# schichor_BP_schema.net
KiCad netlist of a schematic drawn in EAGLE
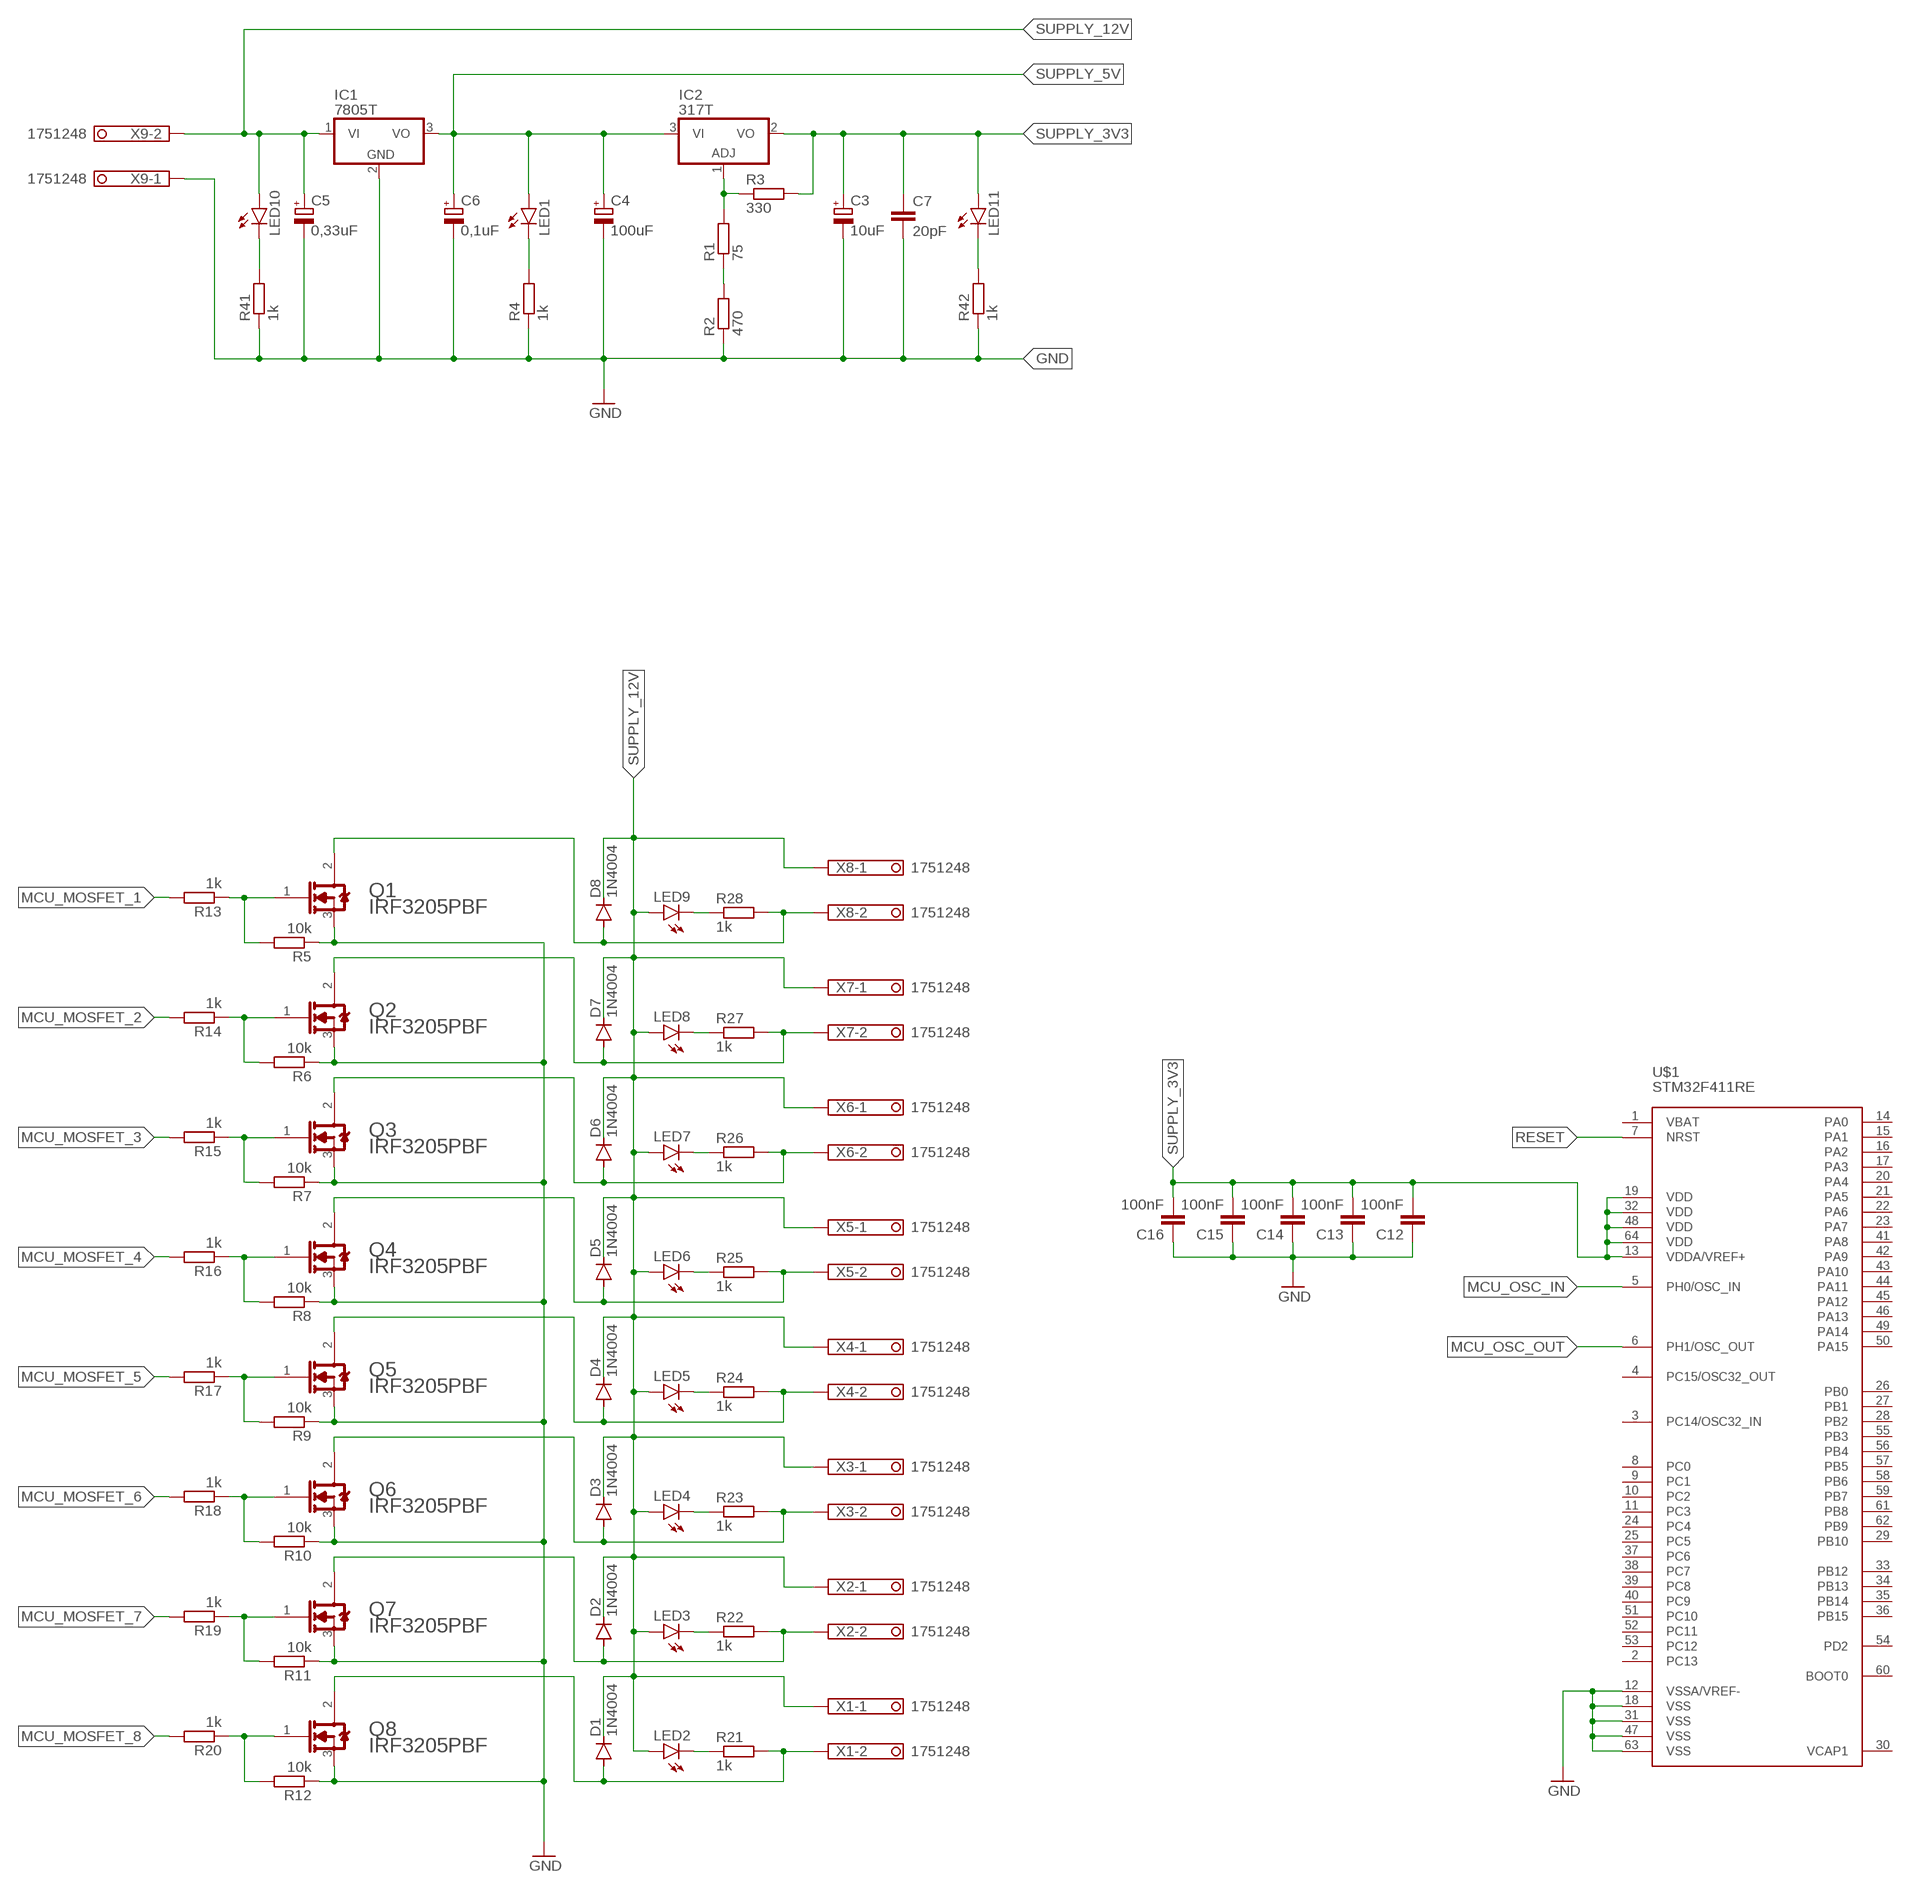
[diagram p0: schematic, sheet 1, part 1 of 2]
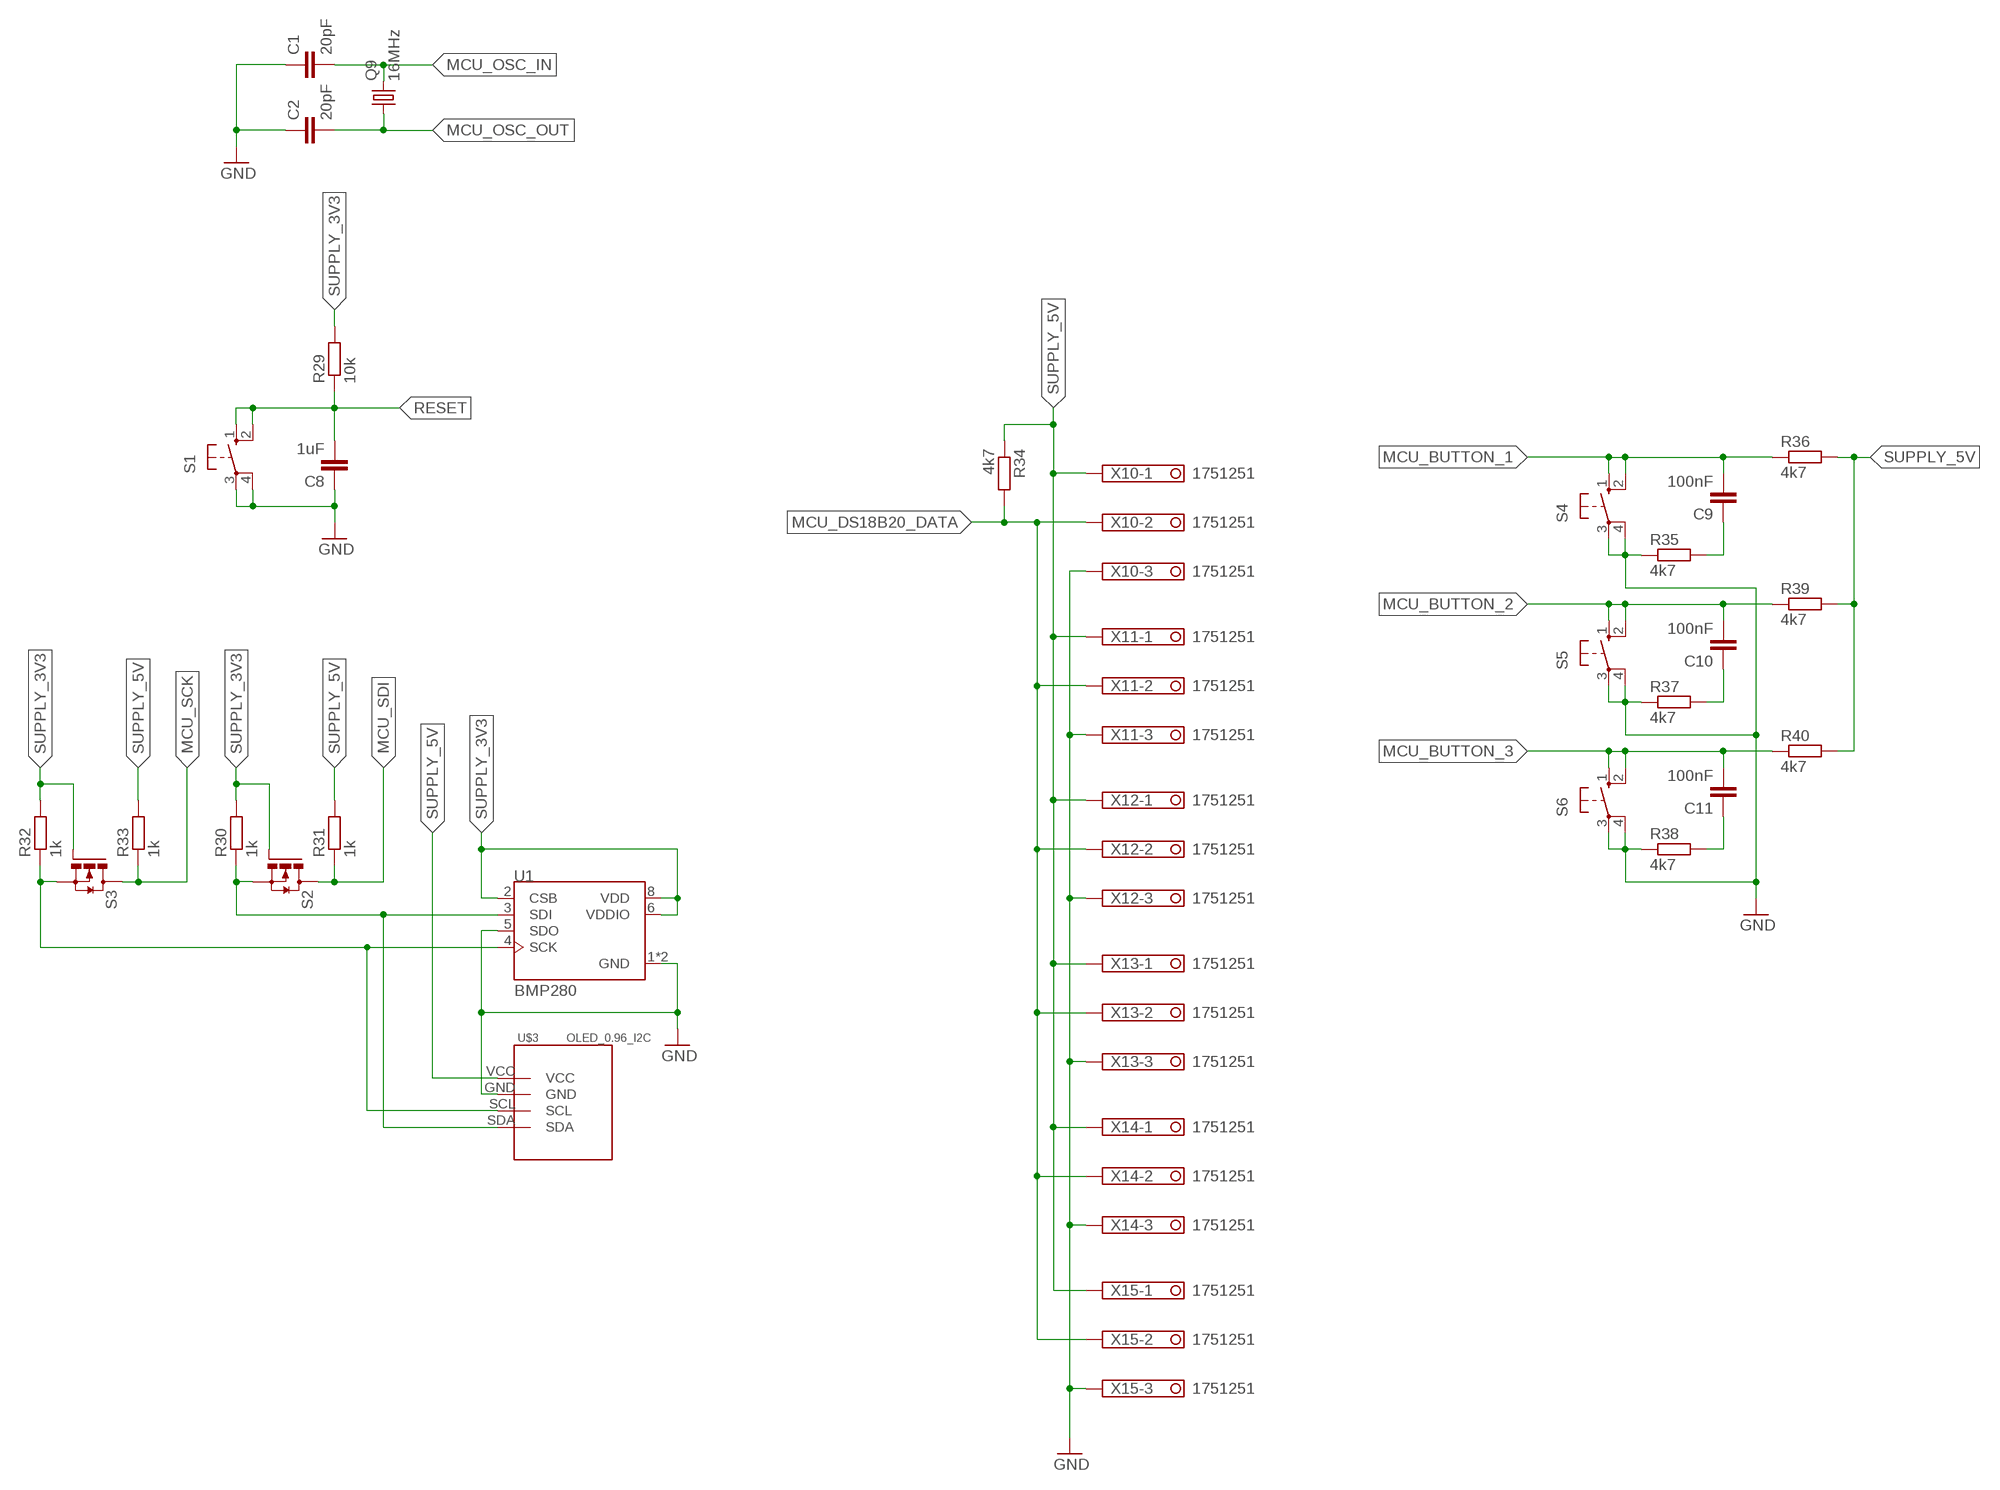
[diagram p1: schematic, sheet 1, part 2 of 2]

(export (version "E")
  (design (tool "Eeschema 10.0.6"))
  (components
    (comp (ref "C1")
      (value "20pF")
      (footprint "eagle-import:C0201")
      (libsource (lib "eagle-import") (part "C-EUC0201"))
    )
    (comp (ref "C2")
      (value "20pF")
      (footprint "eagle-import:C0201")
      (libsource (lib "eagle-import") (part "C-EUC0201"))
    )
    (comp (ref "C3")
      (value "10uF")
      (footprint "eagle-import:085CS_1AR")
      (libsource (lib "eagle-import") (part "CPOL-EU085CS-1AR"))
    )
    (comp (ref "C4")
      (value "100uF")
      (footprint "eagle-import:085CS_1AR")
      (libsource (lib "eagle-import") (part "CPOL-EU085CS-1AR"))
    )
    (comp (ref "C5")
      (value "0,33uF")
      (footprint "eagle-import:085CS_1AR")
      (libsource (lib "eagle-import") (part "CPOL-EU085CS-1AR"))
    )
    (comp (ref "C6")
      (value "0,1uF")
      (footprint "eagle-import:085CS_1AR")
      (libsource (lib "eagle-import") (part "CPOL-EU085CS-1AR"))
    )
    (comp (ref "C7")
      (value "20pF")
      (footprint "eagle-import:C0201")
      (libsource (lib "eagle-import") (part "C-EUC0201"))
    )
    (comp (ref "C8")
      (value "1uF")
      (footprint "eagle-import:C0201")
      (libsource (lib "eagle-import") (part "C-EUC0201"))
    )
    (comp (ref "C9")
      (value "100nF")
      (footprint "eagle-import:C0201")
      (libsource (lib "eagle-import") (part "C-EUC0201"))
    )
    (comp (ref "C10")
      (value "100nF")
      (footprint "eagle-import:C0201")
      (libsource (lib "eagle-import") (part "C-EUC0201"))
    )
    (comp (ref "C11")
      (value "100nF")
      (footprint "eagle-import:C0201")
      (libsource (lib "eagle-import") (part "C-EUC0201"))
    )
    (comp (ref "C12")
      (value "100nF")
      (footprint "eagle-import:C0201")
      (libsource (lib "eagle-import") (part "C-EUC0201"))
    )
    (comp (ref "C13")
      (value "100nF")
      (footprint "eagle-import:C0201")
      (libsource (lib "eagle-import") (part "C-EUC0201"))
    )
    (comp (ref "C14")
      (value "100nF")
      (footprint "eagle-import:C0201")
      (libsource (lib "eagle-import") (part "C-EUC0201"))
    )
    (comp (ref "C15")
      (value "100nF")
      (footprint "eagle-import:C0201")
      (libsource (lib "eagle-import") (part "C-EUC0201"))
    )
    (comp (ref "C16")
      (value "100nF")
      (footprint "eagle-import:C0201")
      (libsource (lib "eagle-import") (part "C-EUC0201"))
    )
    (comp (ref "D1")
      (value "1N4004")
      (footprint "eagle-import:DO41-10")
      (libsource (lib "eagle-import") (part "1N4004"))
    )
    (comp (ref "D2")
      (value "1N4004")
      (footprint "eagle-import:DO41-10")
      (libsource (lib "eagle-import") (part "1N4004"))
    )
    (comp (ref "D3")
      (value "1N4004")
      (footprint "eagle-import:DO41-10")
      (libsource (lib "eagle-import") (part "1N4004"))
    )
    (comp (ref "D4")
      (value "1N4004")
      (footprint "eagle-import:DO41-10")
      (libsource (lib "eagle-import") (part "1N4004"))
    )
    (comp (ref "D5")
      (value "1N4004")
      (footprint "eagle-import:DO41-10")
      (libsource (lib "eagle-import") (part "1N4004"))
    )
    (comp (ref "D6")
      (value "1N4004")
      (footprint "eagle-import:DO41-10")
      (libsource (lib "eagle-import") (part "1N4004"))
    )
    (comp (ref "D7")
      (value "1N4004")
      (footprint "eagle-import:DO41-10")
      (libsource (lib "eagle-import") (part "1N4004"))
    )
    (comp (ref "D8")
      (value "1N4004")
      (footprint "eagle-import:DO41-10")
      (libsource (lib "eagle-import") (part "1N4004"))
    )
    (comp (ref "IC1")
      (value "7805T")
      (footprint "eagle-import:TO220H")
      (libsource (lib "eagle-import") (part "78T05"))
    )
    (comp (ref "IC2")
      (value "317T")
      (footprint "eagle-import:TO220H")
      (libsource (lib "eagle-import") (part "317T"))
    )
    (comp (ref "LED1")
      (value "LED")
      (footprint "eagle-import:SMARTLED-TTW")
      (libsource (lib "eagle-import") (part "LED"))
    )
    (comp (ref "LED2")
      (value "LED")
      (footprint "eagle-import:SMARTLED-TTW")
      (libsource (lib "eagle-import") (part "LED"))
    )
    (comp (ref "LED3")
      (value "LED")
      (footprint "eagle-import:SMARTLED-TTW")
      (libsource (lib "eagle-import") (part "LED"))
    )
    (comp (ref "LED4")
      (value "LED")
      (footprint "eagle-import:SMARTLED-TTW")
      (libsource (lib "eagle-import") (part "LED"))
    )
    (comp (ref "LED5")
      (value "LED")
      (footprint "eagle-import:SMARTLED-TTW")
      (libsource (lib "eagle-import") (part "LED"))
    )
    (comp (ref "LED6")
      (value "LED")
      (footprint "eagle-import:SMARTLED-TTW")
      (libsource (lib "eagle-import") (part "LED"))
    )
    (comp (ref "LED7")
      (value "LED")
      (footprint "eagle-import:SMARTLED-TTW")
      (libsource (lib "eagle-import") (part "LED"))
    )
    (comp (ref "LED8")
      (value "LED")
      (footprint "eagle-import:SMARTLED-TTW")
      (libsource (lib "eagle-import") (part "LED"))
    )
    (comp (ref "LED9")
      (value "LED")
      (footprint "eagle-import:SMARTLED-TTW")
      (libsource (lib "eagle-import") (part "LED"))
    )
    (comp (ref "LED10")
      (value "LED")
      (footprint "eagle-import:SMARTLED-TTW")
      (libsource (lib "eagle-import") (part "LED"))
    )
    (comp (ref "LED11")
      (value "LED")
      (footprint "eagle-import:SMARTLED-TTW")
      (libsource (lib "eagle-import") (part "LED"))
    )
    (comp (ref "Q1")
      (value "INFINEON_IRF3205PBFINFINEON_IRF3205PBF_0_0")
      (footprint "eagle-import:INFINEON_IRF3205PBF_0")
      (fields
        (field (name "DIGIKEY_PART_NUMBER") "IRF3205PBF-ND")
        (field (name "MF") "Infineon")
        (field (name "MOUSER_PART_NUMBER") "942-IRF3205PBF")
      )
      (libsource (lib "eagle-import") (part "INFINEON_IRF3205PBFINFINEON_IRF3205PBF_0_0"))
    )
    (comp (ref "Q2")
      (value "INFINEON_IRF3205PBFINFINEON_IRF3205PBF_0_0")
      (footprint "eagle-import:INFINEON_IRF3205PBF_0")
      (fields
        (field (name "DIGIKEY_PART_NUMBER") "IRF3205PBF-ND")
        (field (name "MF") "Infineon")
        (field (name "MOUSER_PART_NUMBER") "942-IRF3205PBF")
      )
      (libsource (lib "eagle-import") (part "INFINEON_IRF3205PBFINFINEON_IRF3205PBF_0_0"))
    )
    (comp (ref "Q3")
      (value "INFINEON_IRF3205PBFINFINEON_IRF3205PBF_0_0")
      (footprint "eagle-import:INFINEON_IRF3205PBF_0")
      (fields
        (field (name "DIGIKEY_PART_NUMBER") "IRF3205PBF-ND")
        (field (name "MF") "Infineon")
        (field (name "MOUSER_PART_NUMBER") "942-IRF3205PBF")
      )
      (libsource (lib "eagle-import") (part "INFINEON_IRF3205PBFINFINEON_IRF3205PBF_0_0"))
    )
    (comp (ref "Q4")
      (value "INFINEON_IRF3205PBFINFINEON_IRF3205PBF_0_0")
      (footprint "eagle-import:INFINEON_IRF3205PBF_0")
      (fields
        (field (name "DIGIKEY_PART_NUMBER") "IRF3205PBF-ND")
        (field (name "MF") "Infineon")
        (field (name "MOUSER_PART_NUMBER") "942-IRF3205PBF")
      )
      (libsource (lib "eagle-import") (part "INFINEON_IRF3205PBFINFINEON_IRF3205PBF_0_0"))
    )
    (comp (ref "Q5")
      (value "INFINEON_IRF3205PBFINFINEON_IRF3205PBF_0_0")
      (footprint "eagle-import:INFINEON_IRF3205PBF_0")
      (fields
        (field (name "DIGIKEY_PART_NUMBER") "IRF3205PBF-ND")
        (field (name "MF") "Infineon")
        (field (name "MOUSER_PART_NUMBER") "942-IRF3205PBF")
      )
      (libsource (lib "eagle-import") (part "INFINEON_IRF3205PBFINFINEON_IRF3205PBF_0_0"))
    )
    (comp (ref "Q6")
      (value "INFINEON_IRF3205PBFINFINEON_IRF3205PBF_0_0")
      (footprint "eagle-import:INFINEON_IRF3205PBF_0")
      (fields
        (field (name "DIGIKEY_PART_NUMBER") "IRF3205PBF-ND")
        (field (name "MF") "Infineon")
        (field (name "MOUSER_PART_NUMBER") "942-IRF3205PBF")
      )
      (libsource (lib "eagle-import") (part "INFINEON_IRF3205PBFINFINEON_IRF3205PBF_0_0"))
    )
    (comp (ref "Q7")
      (value "INFINEON_IRF3205PBFINFINEON_IRF3205PBF_0_0")
      (footprint "eagle-import:INFINEON_IRF3205PBF_0")
      (fields
        (field (name "DIGIKEY_PART_NUMBER") "IRF3205PBF-ND")
        (field (name "MF") "Infineon")
        (field (name "MOUSER_PART_NUMBER") "942-IRF3205PBF")
      )
      (libsource (lib "eagle-import") (part "INFINEON_IRF3205PBFINFINEON_IRF3205PBF_0_0"))
    )
    (comp (ref "Q8")
      (value "INFINEON_IRF3205PBFINFINEON_IRF3205PBF_0_0")
      (footprint "eagle-import:INFINEON_IRF3205PBF_0")
      (fields
        (field (name "DIGIKEY_PART_NUMBER") "IRF3205PBF-ND")
        (field (name "MF") "Infineon")
        (field (name "MOUSER_PART_NUMBER") "942-IRF3205PBF")
      )
      (libsource (lib "eagle-import") (part "INFINEON_IRF3205PBFINFINEON_IRF3205PBF_0_0"))
    )
    (comp (ref "Q9")
      (value "16MHz")
      (footprint "eagle-import:HC49_S")
      (libsource (lib "eagle-import") (part "CRYSTALHC49S"))
    )
    (comp (ref "R1")
      (value "75")
      (footprint "eagle-import:R1206")
      (libsource (lib "eagle-import") (part "R-EU_R1206"))
    )
    (comp (ref "R2")
      (value "470")
      (footprint "eagle-import:R1206")
      (libsource (lib "eagle-import") (part "R-EU_R1206"))
    )
    (comp (ref "R3")
      (value "330")
      (footprint "eagle-import:R1206")
      (libsource (lib "eagle-import") (part "R-EU_R1206"))
    )
    (comp (ref "R4")
      (value "1k")
      (footprint "eagle-import:R1206")
      (libsource (lib "eagle-import") (part "R-EU_R1206"))
    )
    (comp (ref "R5")
      (value "10k")
      (footprint "eagle-import:R1206")
      (libsource (lib "eagle-import") (part "R-EU_R1206"))
    )
    (comp (ref "R6")
      (value "10k")
      (footprint "eagle-import:R1206")
      (libsource (lib "eagle-import") (part "R-EU_R1206"))
    )
    (comp (ref "R7")
      (value "10k")
      (footprint "eagle-import:R1206")
      (libsource (lib "eagle-import") (part "R-EU_R1206"))
    )
    (comp (ref "R8")
      (value "10k")
      (footprint "eagle-import:R1206")
      (libsource (lib "eagle-import") (part "R-EU_R1206"))
    )
    (comp (ref "R9")
      (value "10k")
      (footprint "eagle-import:R1206")
      (libsource (lib "eagle-import") (part "R-EU_R1206"))
    )
    (comp (ref "R10")
      (value "10k")
      (footprint "eagle-import:R1206")
      (libsource (lib "eagle-import") (part "R-EU_R1206"))
    )
    (comp (ref "R11")
      (value "10k")
      (footprint "eagle-import:R1206")
      (libsource (lib "eagle-import") (part "R-EU_R1206"))
    )
    (comp (ref "R12")
      (value "10k")
      (footprint "eagle-import:R1206")
      (libsource (lib "eagle-import") (part "R-EU_R1206"))
    )
    (comp (ref "R13")
      (value "1k")
      (footprint "eagle-import:R1206")
      (libsource (lib "eagle-import") (part "R-EU_R1206"))
    )
    (comp (ref "R14")
      (value "1k")
      (footprint "eagle-import:R1206")
      (libsource (lib "eagle-import") (part "R-EU_R1206"))
    )
    (comp (ref "R15")
      (value "1k")
      (footprint "eagle-import:R1206")
      (libsource (lib "eagle-import") (part "R-EU_R1206"))
    )
    (comp (ref "R16")
      (value "1k")
      (footprint "eagle-import:R1206")
      (libsource (lib "eagle-import") (part "R-EU_R1206"))
    )
    (comp (ref "R17")
      (value "1k")
      (footprint "eagle-import:R1206")
      (libsource (lib "eagle-import") (part "R-EU_R1206"))
    )
    (comp (ref "R18")
      (value "1k")
      (footprint "eagle-import:R1206")
      (libsource (lib "eagle-import") (part "R-EU_R1206"))
    )
    (comp (ref "R19")
      (value "1k")
      (footprint "eagle-import:R1206")
      (libsource (lib "eagle-import") (part "R-EU_R1206"))
    )
    (comp (ref "R20")
      (value "1k")
      (footprint "eagle-import:R1206")
      (libsource (lib "eagle-import") (part "R-EU_R1206"))
    )
    (comp (ref "R21")
      (value "1k")
      (footprint "eagle-import:R1206")
      (libsource (lib "eagle-import") (part "R-EU_R1206"))
    )
    (comp (ref "R22")
      (value "1k")
      (footprint "eagle-import:R1206")
      (libsource (lib "eagle-import") (part "R-EU_R1206"))
    )
    (comp (ref "R23")
      (value "1k")
      (footprint "eagle-import:R1206")
      (libsource (lib "eagle-import") (part "R-EU_R1206"))
    )
    (comp (ref "R24")
      (value "1k")
      (footprint "eagle-import:R1206")
      (libsource (lib "eagle-import") (part "R-EU_R1206"))
    )
    (comp (ref "R25")
      (value "1k")
      (footprint "eagle-import:R1206")
      (libsource (lib "eagle-import") (part "R-EU_R1206"))
    )
    (comp (ref "R26")
      (value "1k")
      (footprint "eagle-import:R1206")
      (libsource (lib "eagle-import") (part "R-EU_R1206"))
    )
    (comp (ref "R27")
      (value "1k")
      (footprint "eagle-import:R1206")
      (libsource (lib "eagle-import") (part "R-EU_R1206"))
    )
    (comp (ref "R28")
      (value "1k")
      (footprint "eagle-import:R1206")
      (libsource (lib "eagle-import") (part "R-EU_R1206"))
    )
    (comp (ref "R29")
      (value "10k")
      (footprint "eagle-import:R1206")
      (libsource (lib "eagle-import") (part "R-EU_R1206"))
    )
    (comp (ref "R30")
      (value "1k")
      (footprint "eagle-import:R1206")
      (libsource (lib "eagle-import") (part "R-EU_R1206"))
    )
    (comp (ref "R31")
      (value "1k")
      (footprint "eagle-import:R1206")
      (libsource (lib "eagle-import") (part "R-EU_R1206"))
    )
    (comp (ref "R32")
      (value "1k")
      (footprint "eagle-import:R1206")
      (libsource (lib "eagle-import") (part "R-EU_R1206"))
    )
    (comp (ref "R33")
      (value "1k")
      (footprint "eagle-import:R1206")
      (libsource (lib "eagle-import") (part "R-EU_R1206"))
    )
    (comp (ref "R34")
      (value "4k7")
      (footprint "eagle-import:R1206")
      (libsource (lib "eagle-import") (part "R-EU_R1206"))
    )
    (comp (ref "R35")
      (value "4k7")
      (footprint "eagle-import:R1206")
      (libsource (lib "eagle-import") (part "R-EU_R1206"))
    )
    (comp (ref "R36")
      (value "4k7")
      (footprint "eagle-import:R1206")
      (libsource (lib "eagle-import") (part "R-EU_R1206"))
    )
    (comp (ref "R37")
      (value "4k7")
      (footprint "eagle-import:R1206")
      (libsource (lib "eagle-import") (part "R-EU_R1206"))
    )
    (comp (ref "R38")
      (value "4k7")
      (footprint "eagle-import:R1206")
      (libsource (lib "eagle-import") (part "R-EU_R1206"))
    )
    (comp (ref "R39")
      (value "4k7")
      (footprint "eagle-import:R1206")
      (libsource (lib "eagle-import") (part "R-EU_R1206"))
    )
    (comp (ref "R40")
      (value "4k7")
      (footprint "eagle-import:R1206")
      (libsource (lib "eagle-import") (part "R-EU_R1206"))
    )
    (comp (ref "R41")
      (value "1k")
      (footprint "eagle-import:R1206")
      (libsource (lib "eagle-import") (part "R-EU_R1206"))
    )
    (comp (ref "R42")
      (value "1k")
      (footprint "eagle-import:R1206")
      (libsource (lib "eagle-import") (part "R-EU_R1206"))
    )
    (comp (ref "S1")
      (value "10-XX")
      (footprint "eagle-import:B3F-10XX")
      (fields (field (name "MPN") "B3F-1000"))
      (libsource (lib "eagle-import") (part "10-XX"))
    )
    (comp (ref "S2")
      (value "2N7000")
      (footprint "eagle-import:TO-92EXPANDED")
      (fields (field (name "MF") "STMicroelectronics"))
      (libsource (lib "eagle-import") (part "2N7000"))
    )
    (comp (ref "S3")
      (value "2N7000")
      (footprint "eagle-import:TO-92EXPANDED")
      (fields (field (name "MF") "STMicroelectronics"))
      (libsource (lib "eagle-import") (part "2N7000"))
    )
    (comp (ref "S4")
      (value "10-XX")
      (footprint "eagle-import:B3F-10XX")
      (fields (field (name "MPN") "B3F-1000"))
      (libsource (lib "eagle-import") (part "10-XX"))
    )
    (comp (ref "S5")
      (value "10-XX")
      (footprint "eagle-import:B3F-10XX")
      (fields (field (name "MPN") "B3F-1000"))
      (libsource (lib "eagle-import") (part "10-XX"))
    )
    (comp (ref "S6")
      (value "10-XX")
      (footprint "eagle-import:B3F-10XX")
      (fields (field (name "MPN") "B3F-1000"))
      (libsource (lib "eagle-import") (part "10-XX"))
    )
    (comp (ref "U$1")
      (value "STM32F411RE")
      (footprint "eagle-import:LQFP64")
      (libsource (lib "eagle-import") (part "STM32F411XC"))
    )
    (comp (ref "U$3")
      (value "OLED_0.96_I2C")
      (footprint "eagle-import:OLED_0.96_I2C")
      (libsource (lib "eagle-import") (part "OLED_0.96_I2C"))
    )
    (comp (ref "U1")
      (value "BMP280")
      (footprint "eagle-import:XDCR_BMP280")
      (fields (field (name "MF") "Bosch"))
      (libsource (lib "eagle-import") (part "BMP280"))
    )
    (comp (ref "X1")
      (value "1751248")
      (footprint "eagle-import:1751248")
      (libsource (lib "eagle-import") (part "1751248"))
    )
    (comp (ref "X2")
      (value "1751248")
      (footprint "eagle-import:1751248")
      (libsource (lib "eagle-import") (part "1751248"))
    )
    (comp (ref "X3")
      (value "1751248")
      (footprint "eagle-import:1751248")
      (libsource (lib "eagle-import") (part "1751248"))
    )
    (comp (ref "X4")
      (value "1751248")
      (footprint "eagle-import:1751248")
      (libsource (lib "eagle-import") (part "1751248"))
    )
    (comp (ref "X5")
      (value "1751248")
      (footprint "eagle-import:1751248")
      (libsource (lib "eagle-import") (part "1751248"))
    )
    (comp (ref "X6")
      (value "1751248")
      (footprint "eagle-import:1751248")
      (libsource (lib "eagle-import") (part "1751248"))
    )
    (comp (ref "X7")
      (value "1751248")
      (footprint "eagle-import:1751248")
      (libsource (lib "eagle-import") (part "1751248"))
    )
    (comp (ref "X8")
      (value "1751248")
      (footprint "eagle-import:1751248")
      (libsource (lib "eagle-import") (part "1751248"))
    )
    (comp (ref "X9")
      (value "1751248")
      (footprint "eagle-import:1751248")
      (libsource (lib "eagle-import") (part "1751248"))
    )
    (comp (ref "X10")
      (value "1751251")
      (footprint "eagle-import:1751251")
      (libsource (lib "eagle-import") (part "1751251"))
    )
    (comp (ref "X11")
      (value "1751251")
      (footprint "eagle-import:1751251")
      (libsource (lib "eagle-import") (part "1751251"))
    )
    (comp (ref "X12")
      (value "1751251")
      (footprint "eagle-import:1751251")
      (libsource (lib "eagle-import") (part "1751251"))
    )
    (comp (ref "X13")
      (value "1751251")
      (footprint "eagle-import:1751251")
      (libsource (lib "eagle-import") (part "1751251"))
    )
    (comp (ref "X14")
      (value "1751251")
      (footprint "eagle-import:1751251")
      (libsource (lib "eagle-import") (part "1751251"))
    )
    (comp (ref "X15")
      (value "1751251")
      (footprint "eagle-import:1751251")
      (libsource (lib "eagle-import") (part "1751251"))
    )
  )
  (nets
    (net (code "1") (name "GND") (class "Default")
      (node (ref "C1") (pin "1") (pinfunction "1_1") (pintype "passive"))
      (node (ref "C12") (pin "1") (pinfunction "1_1") (pintype "passive"))
      (node (ref "C13") (pin "1") (pinfunction "1_1") (pintype "passive"))
      (node (ref "C14") (pin "1") (pinfunction "1_1") (pintype "passive"))
      (node (ref "C15") (pin "1") (pinfunction "1_1") (pintype "passive"))
      (node (ref "C16") (pin "1") (pinfunction "1_1") (pintype "passive"))
      (node (ref "C2") (pin "1") (pinfunction "1_1") (pintype "passive"))
      (node (ref "C3") (pin "-") (pinfunction "-_-") (pintype "passive"))
      (node (ref "C4") (pin "-") (pinfunction "-_-") (pintype "passive"))
      (node (ref "C5") (pin "-") (pinfunction "-_-") (pintype "passive"))
      (node (ref "C6") (pin "-") (pinfunction "-_-") (pintype "passive"))
      (node (ref "C7") (pin "2") (pinfunction "2_2") (pintype "passive"))
      (node (ref "C8") (pin "1") (pinfunction "1_1") (pintype "passive"))
      (node (ref "IC1") (pin "2") (pinfunction "GND_2") (pintype "passive"))
      (node (ref "Q1") (pin "3") (pinfunction "SOURCE_3") (pintype "passive"))
      (node (ref "Q2") (pin "3") (pinfunction "SOURCE_3") (pintype "passive"))
      (node (ref "Q3") (pin "3") (pinfunction "SOURCE_3") (pintype "passive"))
      (node (ref "Q4") (pin "3") (pinfunction "SOURCE_3") (pintype "passive"))
      (node (ref "Q5") (pin "3") (pinfunction "SOURCE_3") (pintype "passive"))
      (node (ref "Q6") (pin "3") (pinfunction "SOURCE_3") (pintype "passive"))
      (node (ref "Q7") (pin "3") (pinfunction "SOURCE_3") (pintype "passive"))
      (node (ref "Q8") (pin "3") (pinfunction "SOURCE_3") (pintype "passive"))
      (node (ref "R10") (pin "1") (pinfunction "1_1") (pintype "passive"))
      (node (ref "R11") (pin "1") (pinfunction "1_1") (pintype "passive"))
      (node (ref "R12") (pin "1") (pinfunction "1_1") (pintype "passive"))
      (node (ref "R2") (pin "1") (pinfunction "1_1") (pintype "passive"))
      (node (ref "R35") (pin "1") (pinfunction "1_1") (pintype "passive"))
      (node (ref "R37") (pin "1") (pinfunction "1_1") (pintype "passive"))
      (node (ref "R38") (pin "1") (pinfunction "1_1") (pintype "passive"))
      (node (ref "R4") (pin "1") (pinfunction "1_1") (pintype "passive"))
      (node (ref "R41") (pin "1") (pinfunction "1_1") (pintype "passive"))
      (node (ref "R42") (pin "1") (pinfunction "1_1") (pintype "passive"))
      (node (ref "R5") (pin "1") (pinfunction "1_1") (pintype "passive"))
      (node (ref "R6") (pin "1") (pinfunction "1_1") (pintype "passive"))
      (node (ref "R7") (pin "1") (pinfunction "1_1") (pintype "passive"))
      (node (ref "R8") (pin "1") (pinfunction "1_1") (pintype "passive"))
      (node (ref "R9") (pin "1") (pinfunction "1_1") (pintype "passive"))
      (node (ref "S1") (pin "3") (pinfunction "P_3") (pintype "passive"))
      (node (ref "S1") (pin "4") (pinfunction "P1_4") (pintype "passive"))
      (node (ref "S4") (pin "3") (pinfunction "P_3") (pintype "passive"))
      (node (ref "S4") (pin "4") (pinfunction "P1_4") (pintype "passive"))
      (node (ref "S5") (pin "3") (pinfunction "P_3") (pintype "passive"))
      (node (ref "S5") (pin "4") (pinfunction "P1_4") (pintype "passive"))
      (node (ref "S6") (pin "3") (pinfunction "P_3") (pintype "passive"))
      (node (ref "S6") (pin "4") (pinfunction "P1_4") (pintype "passive"))
      (node (ref "U$1") (pin "12") (pinfunction "VSSA/VREF-_12") (pintype "bidirectional"))
      (node (ref "U$1") (pin "18") (pinfunction "VSS_18") (pintype "bidirectional"))
      (node (ref "U$1") (pin "31") (pinfunction "VSS_31") (pintype "bidirectional"))
      (node (ref "U$1") (pin "47") (pinfunction "VSS_47") (pintype "bidirectional"))
      (node (ref "U$1") (pin "63") (pinfunction "VSS_63") (pintype "bidirectional"))
      (node (ref "U$3") (pin "GND") (pinfunction "GND_GND") (pintype "bidirectional"))
      (node (ref "U1") (pin "1") (pinfunction "GND_1") (pintype "power_in"))
      (node (ref "U1") (pin "5") (pinfunction "SDO_5") (pintype "bidirectional"))
      (node (ref "U1") (pin "7") (pinfunction "GND_7") (pintype "power_in"))
      (node (ref "X10") (pin "3") (pinfunction "K_3") (pintype "passive"))
      (node (ref "X11") (pin "3") (pinfunction "K_3") (pintype "passive"))
      (node (ref "X12") (pin "3") (pinfunction "K_3") (pintype "passive"))
      (node (ref "X13") (pin "3") (pinfunction "K_3") (pintype "passive"))
      (node (ref "X14") (pin "3") (pinfunction "K_3") (pintype "passive"))
      (node (ref "X15") (pin "3") (pinfunction "K_3") (pintype "passive"))
      (node (ref "X9") (pin "1") (pinfunction "K_1") (pintype "passive"))
    )
    (net (code "2") (name "MCU_BUTTON_1") (class "Default")
      (node (ref "C9") (pin "2") (pinfunction "2_2") (pintype "passive"))
      (node (ref "R36") (pin "1") (pinfunction "1_1") (pintype "passive"))
      (node (ref "S4") (pin "1") (pinfunction "S_1") (pintype "passive"))
      (node (ref "S4") (pin "2") (pinfunction "S1_2") (pintype "passive"))
    )
    (net (code "3") (name "MCU_BUTTON_2") (class "Default")
      (node (ref "C10") (pin "2") (pinfunction "2_2") (pintype "passive"))
      (node (ref "R39") (pin "1") (pinfunction "1_1") (pintype "passive"))
      (node (ref "S5") (pin "1") (pinfunction "S_1") (pintype "passive"))
      (node (ref "S5") (pin "2") (pinfunction "S1_2") (pintype "passive"))
    )
    (net (code "4") (name "MCU_BUTTON_3") (class "Default")
      (node (ref "C11") (pin "2") (pinfunction "2_2") (pintype "passive"))
      (node (ref "R40") (pin "1") (pinfunction "1_1") (pintype "passive"))
      (node (ref "S6") (pin "1") (pinfunction "S_1") (pintype "passive"))
      (node (ref "S6") (pin "2") (pinfunction "S1_2") (pintype "passive"))
    )
    (net (code "5") (name "MCU_DS18B20_DATA") (class "Default")
      (node (ref "R34") (pin "2") (pinfunction "2_2") (pintype "passive"))
      (node (ref "X10") (pin "2") (pinfunction "K_2") (pintype "passive"))
      (node (ref "X11") (pin "2") (pinfunction "K_2") (pintype "passive"))
      (node (ref "X12") (pin "2") (pinfunction "K_2") (pintype "passive"))
      (node (ref "X13") (pin "2") (pinfunction "K_2") (pintype "passive"))
      (node (ref "X14") (pin "2") (pinfunction "K_2") (pintype "passive"))
      (node (ref "X15") (pin "2") (pinfunction "K_2") (pintype "passive"))
    )
    (net (code "6") (name "MCU_MOSFET_1") (class "Default")
      (node (ref "R13") (pin "2") (pinfunction "2_2") (pintype "passive"))
    )
    (net (code "7") (name "MCU_MOSFET_2") (class "Default")
      (node (ref "R14") (pin "2") (pinfunction "2_2") (pintype "passive"))
    )
    (net (code "8") (name "MCU_MOSFET_3") (class "Default")
      (node (ref "R15") (pin "2") (pinfunction "2_2") (pintype "passive"))
    )
    (net (code "9") (name "MCU_MOSFET_4") (class "Default")
      (node (ref "R16") (pin "2") (pinfunction "2_2") (pintype "passive"))
    )
    (net (code "10") (name "MCU_MOSFET_5") (class "Default")
      (node (ref "R17") (pin "2") (pinfunction "2_2") (pintype "passive"))
    )
    (net (code "11") (name "MCU_MOSFET_6") (class "Default")
      (node (ref "R18") (pin "2") (pinfunction "2_2") (pintype "passive"))
    )
    (net (code "12") (name "MCU_MOSFET_7") (class "Default")
      (node (ref "R19") (pin "2") (pinfunction "2_2") (pintype "passive"))
    )
    (net (code "13") (name "MCU_MOSFET_8") (class "Default")
      (node (ref "R20") (pin "2") (pinfunction "2_2") (pintype "passive"))
    )
    (net (code "14") (name "MCU_OSC_IN") (class "Default")
      (node (ref "C1") (pin "2") (pinfunction "2_2") (pintype "passive"))
      (node (ref "Q9") (pin "2") (pinfunction "2_2") (pintype "passive"))
      (node (ref "U$1") (pin "5") (pinfunction "PH0/OSC_IN_5") (pintype "bidirectional"))
    )
    (net (code "15") (name "MCU_OSC_OUT") (class "Default")
      (node (ref "C2") (pin "2") (pinfunction "2_2") (pintype "passive"))
      (node (ref "Q9") (pin "1") (pinfunction "1_1") (pintype "passive"))
      (node (ref "U$1") (pin "6") (pinfunction "PH1/OSC_OUT_6") (pintype "bidirectional"))
    )
    (net (code "16") (name "MCU_SCK") (class "Default")
      (node (ref "R33") (pin "1") (pinfunction "1_1") (pintype "passive"))
      (node (ref "S3") (pin "1") (pinfunction "D_1") (pintype "passive"))
    )
    (net (code "17") (name "MCU_SDI") (class "Default")
      (node (ref "R31") (pin "1") (pinfunction "1_1") (pintype "passive"))
      (node (ref "S2") (pin "1") (pinfunction "D_1") (pintype "passive"))
    )
    (net (code "18") (name "Net-(C9-Pad1)") (class "Default")
      (node (ref "C9") (pin "1") (pinfunction "1_1") (pintype "passive"))
      (node (ref "R35") (pin "2") (pinfunction "2_2") (pintype "passive"))
    )
    (net (code "19") (name "Net-(C10-Pad1)") (class "Default")
      (node (ref "C10") (pin "1") (pinfunction "1_1") (pintype "passive"))
      (node (ref "R37") (pin "2") (pinfunction "2_2") (pintype "passive"))
    )
    (net (code "20") (name "Net-(C11-Pad1)") (class "Default")
      (node (ref "C11") (pin "1") (pinfunction "1_1") (pintype "passive"))
      (node (ref "R38") (pin "2") (pinfunction "2_2") (pintype "passive"))
    )
    (net (code "21") (name "Net-(IC2-ADJ)") (class "Default")
      (node (ref "IC2") (pin "1") (pinfunction "ADJ_1") (pintype "input"))
      (node (ref "R1") (pin "2") (pinfunction "2_2") (pintype "passive"))
      (node (ref "R3") (pin "1") (pinfunction "1_1") (pintype "passive"))
    )
    (net (code "22") (name "Net-(LED1-C)") (class "Default")
      (node (ref "LED1") (pin "C@1") (pinfunction "C_C@1") (pintype "passive"))
      (node (ref "R4") (pin "2") (pinfunction "2_2") (pintype "passive"))
    )
    (net (code "23") (name "Net-(LED2-C)") (class "Default")
      (node (ref "LED2") (pin "C@1") (pinfunction "C_C@1") (pintype "passive"))
      (node (ref "R21") (pin "1") (pinfunction "1_1") (pintype "passive"))
    )
    (net (code "24") (name "Net-(LED3-C)") (class "Default")
      (node (ref "LED3") (pin "C@1") (pinfunction "C_C@1") (pintype "passive"))
      (node (ref "R22") (pin "1") (pinfunction "1_1") (pintype "passive"))
    )
    (net (code "25") (name "Net-(LED4-C)") (class "Default")
      (node (ref "LED4") (pin "C@1") (pinfunction "C_C@1") (pintype "passive"))
      (node (ref "R23") (pin "1") (pinfunction "1_1") (pintype "passive"))
    )
    (net (code "26") (name "Net-(LED5-C)") (class "Default")
      (node (ref "LED5") (pin "C@1") (pinfunction "C_C@1") (pintype "passive"))
      (node (ref "R24") (pin "1") (pinfunction "1_1") (pintype "passive"))
    )
    (net (code "27") (name "Net-(LED6-C)") (class "Default")
      (node (ref "LED6") (pin "C@1") (pinfunction "C_C@1") (pintype "passive"))
      (node (ref "R25") (pin "1") (pinfunction "1_1") (pintype "passive"))
    )
    (net (code "28") (name "Net-(LED7-C)") (class "Default")
      (node (ref "LED7") (pin "C@1") (pinfunction "C_C@1") (pintype "passive"))
      (node (ref "R26") (pin "1") (pinfunction "1_1") (pintype "passive"))
    )
    (net (code "29") (name "Net-(LED8-C)") (class "Default")
      (node (ref "LED8") (pin "C@1") (pinfunction "C_C@1") (pintype "passive"))
      (node (ref "R27") (pin "1") (pinfunction "1_1") (pintype "passive"))
    )
    (net (code "30") (name "Net-(LED9-C)") (class "Default")
      (node (ref "LED9") (pin "C@1") (pinfunction "C_C@1") (pintype "passive"))
      (node (ref "R28") (pin "1") (pinfunction "1_1") (pintype "passive"))
    )
    (net (code "31") (name "Net-(LED10-C)") (class "Default")
      (node (ref "LED10") (pin "C@1") (pinfunction "C_C@1") (pintype "passive"))
      (node (ref "R41") (pin "2") (pinfunction "2_2") (pintype "passive"))
    )
    (net (code "32") (name "Net-(LED11-C)") (class "Default")
      (node (ref "LED11") (pin "C@1") (pinfunction "C_C@1") (pintype "passive"))
      (node (ref "R42") (pin "2") (pinfunction "2_2") (pintype "passive"))
    )
    (net (code "33") (name "Net-(Q1-DRAIN)") (class "Default")
      (node (ref "D8") (pin "A") (pinfunction "A_A") (pintype "passive"))
      (node (ref "Q1") (pin "2") (pinfunction "DRAIN_2") (pintype "passive"))
      (node (ref "R28") (pin "2") (pinfunction "2_2") (pintype "passive"))
      (node (ref "X8") (pin "2") (pinfunction "K_2") (pintype "passive"))
    )
    (net (code "34") (name "Net-(Q1-GATE)") (class "Default")
      (node (ref "Q1") (pin "1") (pinfunction "GATE_1") (pintype "passive"))
      (node (ref "R13") (pin "1") (pinfunction "1_1") (pintype "passive"))
      (node (ref "R5") (pin "2") (pinfunction "2_2") (pintype "passive"))
    )
    (net (code "35") (name "Net-(Q2-DRAIN)") (class "Default")
      (node (ref "D7") (pin "A") (pinfunction "A_A") (pintype "passive"))
      (node (ref "Q2") (pin "2") (pinfunction "DRAIN_2") (pintype "passive"))
      (node (ref "R27") (pin "2") (pinfunction "2_2") (pintype "passive"))
      (node (ref "X7") (pin "2") (pinfunction "K_2") (pintype "passive"))
    )
    (net (code "36") (name "Net-(Q2-GATE)") (class "Default")
      (node (ref "Q2") (pin "1") (pinfunction "GATE_1") (pintype "passive"))
      (node (ref "R14") (pin "1") (pinfunction "1_1") (pintype "passive"))
      (node (ref "R6") (pin "2") (pinfunction "2_2") (pintype "passive"))
    )
    (net (code "37") (name "Net-(Q3-DRAIN)") (class "Default")
      (node (ref "D6") (pin "A") (pinfunction "A_A") (pintype "passive"))
      (node (ref "Q3") (pin "2") (pinfunction "DRAIN_2") (pintype "passive"))
      (node (ref "R26") (pin "2") (pinfunction "2_2") (pintype "passive"))
      (node (ref "X6") (pin "2") (pinfunction "K_2") (pintype "passive"))
    )
    (net (code "38") (name "Net-(Q3-GATE)") (class "Default")
      (node (ref "Q3") (pin "1") (pinfunction "GATE_1") (pintype "passive"))
      (node (ref "R15") (pin "1") (pinfunction "1_1") (pintype "passive"))
      (node (ref "R7") (pin "2") (pinfunction "2_2") (pintype "passive"))
    )
    (net (code "39") (name "Net-(Q4-DRAIN)") (class "Default")
      (node (ref "D5") (pin "A") (pinfunction "A_A") (pintype "passive"))
      (node (ref "Q4") (pin "2") (pinfunction "DRAIN_2") (pintype "passive"))
      (node (ref "R25") (pin "2") (pinfunction "2_2") (pintype "passive"))
      (node (ref "X5") (pin "2") (pinfunction "K_2") (pintype "passive"))
    )
    (net (code "40") (name "Net-(Q4-GATE)") (class "Default")
      (node (ref "Q4") (pin "1") (pinfunction "GATE_1") (pintype "passive"))
      (node (ref "R16") (pin "1") (pinfunction "1_1") (pintype "passive"))
      (node (ref "R8") (pin "2") (pinfunction "2_2") (pintype "passive"))
    )
    (net (code "41") (name "Net-(Q5-DRAIN)") (class "Default")
      (node (ref "D4") (pin "A") (pinfunction "A_A") (pintype "passive"))
      (node (ref "Q5") (pin "2") (pinfunction "DRAIN_2") (pintype "passive"))
      (node (ref "R24") (pin "2") (pinfunction "2_2") (pintype "passive"))
      (node (ref "X4") (pin "2") (pinfunction "K_2") (pintype "passive"))
    )
    (net (code "42") (name "Net-(Q5-GATE)") (class "Default")
      (node (ref "Q5") (pin "1") (pinfunction "GATE_1") (pintype "passive"))
      (node (ref "R17") (pin "1") (pinfunction "1_1") (pintype "passive"))
      (node (ref "R9") (pin "2") (pinfunction "2_2") (pintype "passive"))
    )
    (net (code "43") (name "Net-(Q6-DRAIN)") (class "Default")
      (node (ref "D3") (pin "A") (pinfunction "A_A") (pintype "passive"))
      (node (ref "Q6") (pin "2") (pinfunction "DRAIN_2") (pintype "passive"))
      (node (ref "R23") (pin "2") (pinfunction "2_2") (pintype "passive"))
      (node (ref "X3") (pin "2") (pinfunction "K_2") (pintype "passive"))
    )
    (net (code "44") (name "Net-(Q6-GATE)") (class "Default")
      (node (ref "Q6") (pin "1") (pinfunction "GATE_1") (pintype "passive"))
      (node (ref "R10") (pin "2") (pinfunction "2_2") (pintype "passive"))
      (node (ref "R18") (pin "1") (pinfunction "1_1") (pintype "passive"))
    )
    (net (code "45") (name "Net-(Q7-DRAIN)") (class "Default")
      (node (ref "D2") (pin "A") (pinfunction "A_A") (pintype "passive"))
      (node (ref "Q7") (pin "2") (pinfunction "DRAIN_2") (pintype "passive"))
      (node (ref "R22") (pin "2") (pinfunction "2_2") (pintype "passive"))
      (node (ref "X2") (pin "2") (pinfunction "K_2") (pintype "passive"))
    )
    (net (code "46") (name "Net-(Q7-GATE)") (class "Default")
      (node (ref "Q7") (pin "1") (pinfunction "GATE_1") (pintype "passive"))
      (node (ref "R11") (pin "2") (pinfunction "2_2") (pintype "passive"))
      (node (ref "R19") (pin "1") (pinfunction "1_1") (pintype "passive"))
    )
    (net (code "47") (name "Net-(Q8-DRAIN)") (class "Default")
      (node (ref "D1") (pin "A") (pinfunction "A_A") (pintype "passive"))
      (node (ref "Q8") (pin "2") (pinfunction "DRAIN_2") (pintype "passive"))
      (node (ref "R21") (pin "2") (pinfunction "2_2") (pintype "passive"))
      (node (ref "X1") (pin "2") (pinfunction "K_2") (pintype "passive"))
    )
    (net (code "48") (name "Net-(Q8-GATE)") (class "Default")
      (node (ref "Q8") (pin "1") (pinfunction "GATE_1") (pintype "passive"))
      (node (ref "R12") (pin "2") (pinfunction "2_2") (pintype "passive"))
      (node (ref "R20") (pin "1") (pinfunction "1_1") (pintype "passive"))
    )
    (net (code "49") (name "Net-(R1-Pad1)") (class "Default")
      (node (ref "R1") (pin "1") (pinfunction "1_1") (pintype "passive"))
      (node (ref "R2") (pin "2") (pinfunction "2_2") (pintype "passive"))
    )
    (net (code "50") (name "Net-(S2-S)") (class "Default")
      (node (ref "R30") (pin "1") (pinfunction "1_1") (pintype "passive"))
      (node (ref "S2") (pin "3") (pinfunction "S_3") (pintype "passive"))
      (node (ref "U$3") (pin "SDA") (pinfunction "SDA_SDA") (pintype "bidirectional"))
      (node (ref "U1") (pin "3") (pinfunction "SDI_3") (pintype "bidirectional"))
    )
    (net (code "51") (name "Net-(S3-S)") (class "Default")
      (node (ref "R32") (pin "1") (pinfunction "1_1") (pintype "passive"))
      (node (ref "S3") (pin "3") (pinfunction "S_3") (pintype "passive"))
      (node (ref "U$3") (pin "SCL") (pinfunction "SCL_SCL") (pintype "bidirectional"))
      (node (ref "U1") (pin "4") (pinfunction "SCK_4") (pintype "input"))
    )
    (net (code "52") (name "RESET") (class "Default")
      (node (ref "C8") (pin "2") (pinfunction "2_2") (pintype "passive"))
      (node (ref "R29") (pin "1") (pinfunction "1_1") (pintype "passive"))
      (node (ref "S1") (pin "1") (pinfunction "S_1") (pintype "passive"))
      (node (ref "S1") (pin "2") (pinfunction "S1_2") (pintype "passive"))
      (node (ref "U$1") (pin "7") (pinfunction "NRST_7") (pintype "bidirectional"))
    )
    (net (code "53") (name "SUPPLY_3V3") (class "Default")
      (node (ref "C12") (pin "2") (pinfunction "2_2") (pintype "passive"))
      (node (ref "C13") (pin "2") (pinfunction "2_2") (pintype "passive"))
      (node (ref "C14") (pin "2") (pinfunction "2_2") (pintype "passive"))
      (node (ref "C15") (pin "2") (pinfunction "2_2") (pintype "passive"))
      (node (ref "C16") (pin "2") (pinfunction "2_2") (pintype "passive"))
      (node (ref "C3") (pin "+") (pinfunction "+_+") (pintype "passive"))
      (node (ref "C7") (pin "1") (pinfunction "1_1") (pintype "passive"))
      (node (ref "IC2") (pin "2") (pinfunction "VO_2") (pintype "passive"))
      (node (ref "LED11") (pin "A@1") (pinfunction "A_A@1") (pintype "passive"))
      (node (ref "R29") (pin "2") (pinfunction "2_2") (pintype "passive"))
      (node (ref "R3") (pin "2") (pinfunction "2_2") (pintype "passive"))
      (node (ref "R30") (pin "2") (pinfunction "2_2") (pintype "passive"))
      (node (ref "R32") (pin "2") (pinfunction "2_2") (pintype "passive"))
      (node (ref "S2") (pin "2") (pinfunction "G_2") (pintype "passive"))
      (node (ref "S3") (pin "2") (pinfunction "G_2") (pintype "passive"))
      (node (ref "U$1") (pin "13") (pinfunction "VDDA/VREF+_13") (pintype "bidirectional"))
      (node (ref "U$1") (pin "19") (pinfunction "VDD_19") (pintype "bidirectional"))
      (node (ref "U$1") (pin "32") (pinfunction "VDD_32") (pintype "bidirectional"))
      (node (ref "U$1") (pin "48") (pinfunction "VDD_48") (pintype "bidirectional"))
      (node (ref "U$1") (pin "64") (pinfunction "VDD_64") (pintype "bidirectional"))
      (node (ref "U1") (pin "2") (pinfunction "CSB_2") (pintype "input"))
      (node (ref "U1") (pin "6") (pinfunction "VDDIO_6") (pintype "power_in"))
      (node (ref "U1") (pin "8") (pinfunction "VDD_8") (pintype "power_in"))
    )
    (net (code "54") (name "SUPPLY_5V") (class "Default")
      (node (ref "C4") (pin "+") (pinfunction "+_+") (pintype "passive"))
      (node (ref "C6") (pin "+") (pinfunction "+_+") (pintype "passive"))
      (node (ref "IC1") (pin "3") (pinfunction "VO_3") (pintype "passive"))
      (node (ref "IC2") (pin "3") (pinfunction "VI_3") (pintype "input"))
      (node (ref "LED1") (pin "A@1") (pinfunction "A_A@1") (pintype "passive"))
      (node (ref "R31") (pin "2") (pinfunction "2_2") (pintype "passive"))
      (node (ref "R33") (pin "2") (pinfunction "2_2") (pintype "passive"))
      (node (ref "R34") (pin "1") (pinfunction "1_1") (pintype "passive"))
      (node (ref "R36") (pin "2") (pinfunction "2_2") (pintype "passive"))
      (node (ref "R39") (pin "2") (pinfunction "2_2") (pintype "passive"))
      (node (ref "R40") (pin "2") (pinfunction "2_2") (pintype "passive"))
      (node (ref "U$3") (pin "VCC") (pinfunction "VCC_VCC") (pintype "bidirectional"))
      (node (ref "X10") (pin "1") (pinfunction "K_1") (pintype "passive"))
      (node (ref "X11") (pin "1") (pinfunction "K_1") (pintype "passive"))
      (node (ref "X12") (pin "1") (pinfunction "K_1") (pintype "passive"))
      (node (ref "X13") (pin "1") (pinfunction "K_1") (pintype "passive"))
      (node (ref "X14") (pin "1") (pinfunction "K_1") (pintype "passive"))
      (node (ref "X15") (pin "1") (pinfunction "K_1") (pintype "passive"))
    )
    (net (code "55") (name "SUPPLY_12V") (class "Default")
      (node (ref "C5") (pin "+") (pinfunction "+_+") (pintype "passive"))
      (node (ref "D1") (pin "C") (pinfunction "C_C") (pintype "passive"))
      (node (ref "D2") (pin "C") (pinfunction "C_C") (pintype "passive"))
      (node (ref "D3") (pin "C") (pinfunction "C_C") (pintype "passive"))
      (node (ref "D4") (pin "C") (pinfunction "C_C") (pintype "passive"))
      (node (ref "D5") (pin "C") (pinfunction "C_C") (pintype "passive"))
      (node (ref "D6") (pin "C") (pinfunction "C_C") (pintype "passive"))
      (node (ref "D7") (pin "C") (pinfunction "C_C") (pintype "passive"))
      (node (ref "D8") (pin "C") (pinfunction "C_C") (pintype "passive"))
      (node (ref "IC1") (pin "1") (pinfunction "VI_1") (pintype "input"))
      (node (ref "LED10") (pin "A@1") (pinfunction "A_A@1") (pintype "passive"))
      (node (ref "LED2") (pin "A@1") (pinfunction "A_A@1") (pintype "passive"))
      (node (ref "LED3") (pin "A@1") (pinfunction "A_A@1") (pintype "passive"))
      (node (ref "LED4") (pin "A@1") (pinfunction "A_A@1") (pintype "passive"))
      (node (ref "LED5") (pin "A@1") (pinfunction "A_A@1") (pintype "passive"))
      (node (ref "LED6") (pin "A@1") (pinfunction "A_A@1") (pintype "passive"))
      (node (ref "LED7") (pin "A@1") (pinfunction "A_A@1") (pintype "passive"))
      (node (ref "LED8") (pin "A@1") (pinfunction "A_A@1") (pintype "passive"))
      (node (ref "LED9") (pin "A@1") (pinfunction "A_A@1") (pintype "passive"))
      (node (ref "X1") (pin "1") (pinfunction "K_1") (pintype "passive"))
      (node (ref "X2") (pin "1") (pinfunction "K_1") (pintype "passive"))
      (node (ref "X3") (pin "1") (pinfunction "K_1") (pintype "passive"))
      (node (ref "X4") (pin "1") (pinfunction "K_1") (pintype "passive"))
      (node (ref "X5") (pin "1") (pinfunction "K_1") (pintype "passive"))
      (node (ref "X6") (pin "1") (pinfunction "K_1") (pintype "passive"))
      (node (ref "X7") (pin "1") (pinfunction "K_1") (pintype "passive"))
      (node (ref "X8") (pin "1") (pinfunction "K_1") (pintype "passive"))
      (node (ref "X9") (pin "2") (pinfunction "K_2") (pintype "passive"))
    )
    (net (code "56") (name "unconnected-(U$1-BOOT0-Pad60)") (class "Default")
      (node (ref "U$1") (pin "60") (pinfunction "BOOT0_60") (pintype "bidirectional"))
    )
    (net (code "57") (name "unconnected-(U$1-PA0-Pad14)") (class "Default")
      (node (ref "U$1") (pin "14") (pinfunction "PA0_14") (pintype "bidirectional"))
    )
    (net (code "58") (name "unconnected-(U$1-PA1-Pad15)") (class "Default")
      (node (ref "U$1") (pin "15") (pinfunction "PA1_15") (pintype "bidirectional"))
    )
    (net (code "59") (name "unconnected-(U$1-PA2-Pad16)") (class "Default")
      (node (ref "U$1") (pin "16") (pinfunction "PA2_16") (pintype "bidirectional"))
    )
    (net (code "60") (name "unconnected-(U$1-PA3-Pad17)") (class "Default")
      (node (ref "U$1") (pin "17") (pinfunction "PA3_17") (pintype "bidirectional"))
    )
    (net (code "61") (name "unconnected-(U$1-PA4-Pad20)") (class "Default")
      (node (ref "U$1") (pin "20") (pinfunction "PA4_20") (pintype "bidirectional"))
    )
    (net (code "62") (name "unconnected-(U$1-PA5-Pad21)") (class "Default")
      (node (ref "U$1") (pin "21") (pinfunction "PA5_21") (pintype "bidirectional"))
    )
    (net (code "63") (name "unconnected-(U$1-PA6-Pad22)") (class "Default")
      (node (ref "U$1") (pin "22") (pinfunction "PA6_22") (pintype "bidirectional"))
    )
    (net (code "64") (name "unconnected-(U$1-PA7-Pad23)") (class "Default")
      (node (ref "U$1") (pin "23") (pinfunction "PA7_23") (pintype "bidirectional"))
    )
    (net (code "65") (name "unconnected-(U$1-PA8-Pad41)") (class "Default")
      (node (ref "U$1") (pin "41") (pinfunction "PA8_41") (pintype "bidirectional"))
    )
    (net (code "66") (name "unconnected-(U$1-PA9-Pad42)") (class "Default")
      (node (ref "U$1") (pin "42") (pinfunction "PA9_42") (pintype "bidirectional"))
    )
    (net (code "67") (name "unconnected-(U$1-PA10-Pad43)") (class "Default")
      (node (ref "U$1") (pin "43") (pinfunction "PA10_43") (pintype "bidirectional"))
    )
    (net (code "68") (name "unconnected-(U$1-PA11-Pad44)") (class "Default")
      (node (ref "U$1") (pin "44") (pinfunction "PA11_44") (pintype "bidirectional"))
    )
    (net (code "69") (name "unconnected-(U$1-PA12-Pad45)") (class "Default")
      (node (ref "U$1") (pin "45") (pinfunction "PA12_45") (pintype "bidirectional"))
    )
    (net (code "70") (name "unconnected-(U$1-PA13-Pad46)") (class "Default")
      (node (ref "U$1") (pin "46") (pinfunction "PA13_46") (pintype "bidirectional"))
    )
    (net (code "71") (name "unconnected-(U$1-PA14-Pad49)") (class "Default")
      (node (ref "U$1") (pin "49") (pinfunction "PA14_49") (pintype "bidirectional"))
    )
    (net (code "72") (name "unconnected-(U$1-PA15-Pad50)") (class "Default")
      (node (ref "U$1") (pin "50") (pinfunction "PA15_50") (pintype "bidirectional"))
    )
    (net (code "73") (name "unconnected-(U$1-PB0-Pad26)") (class "Default")
      (node (ref "U$1") (pin "26") (pinfunction "PB0_26") (pintype "bidirectional"))
    )
    (net (code "74") (name "unconnected-(U$1-PB1-Pad27)") (class "Default")
      (node (ref "U$1") (pin "27") (pinfunction "PB1_27") (pintype "bidirectional"))
    )
    (net (code "75") (name "unconnected-(U$1-PB2-Pad28)") (class "Default")
      (node (ref "U$1") (pin "28") (pinfunction "PB2_28") (pintype "bidirectional"))
    )
    (net (code "76") (name "unconnected-(U$1-PB3-Pad55)") (class "Default")
      (node (ref "U$1") (pin "55") (pinfunction "PB3_55") (pintype "bidirectional"))
    )
    (net (code "77") (name "unconnected-(U$1-PB4-Pad56)") (class "Default")
      (node (ref "U$1") (pin "56") (pinfunction "PB4_56") (pintype "bidirectional"))
    )
    (net (code "78") (name "unconnected-(U$1-PB5-Pad57)") (class "Default")
      (node (ref "U$1") (pin "57") (pinfunction "PB5_57") (pintype "bidirectional"))
    )
    (net (code "79") (name "unconnected-(U$1-PB6-Pad58)") (class "Default")
      (node (ref "U$1") (pin "58") (pinfunction "PB6_58") (pintype "bidirectional"))
    )
    (net (code "80") (name "unconnected-(U$1-PB7-Pad59)") (class "Default")
      (node (ref "U$1") (pin "59") (pinfunction "PB7_59") (pintype "bidirectional"))
    )
    (net (code "81") (name "unconnected-(U$1-PB8-Pad61)") (class "Default")
      (node (ref "U$1") (pin "61") (pinfunction "PB8_61") (pintype "bidirectional"))
    )
    (net (code "82") (name "unconnected-(U$1-PB9-Pad62)") (class "Default")
      (node (ref "U$1") (pin "62") (pinfunction "PB9_62") (pintype "bidirectional"))
    )
    (net (code "83") (name "unconnected-(U$1-PB10-Pad29)") (class "Default")
      (node (ref "U$1") (pin "29") (pinfunction "PB10_29") (pintype "bidirectional"))
    )
    (net (code "84") (name "unconnected-(U$1-PB12-Pad33)") (class "Default")
      (node (ref "U$1") (pin "33") (pinfunction "PB12_33") (pintype "bidirectional"))
    )
    (net (code "85") (name "unconnected-(U$1-PB13-Pad34)") (class "Default")
      (node (ref "U$1") (pin "34") (pinfunction "PB13_34") (pintype "bidirectional"))
    )
    (net (code "86") (name "unconnected-(U$1-PB14-Pad35)") (class "Default")
      (node (ref "U$1") (pin "35") (pinfunction "PB14_35") (pintype "bidirectional"))
    )
    (net (code "87") (name "unconnected-(U$1-PB15-Pad36)") (class "Default")
      (node (ref "U$1") (pin "36") (pinfunction "PB15_36") (pintype "bidirectional"))
    )
    (net (code "88") (name "unconnected-(U$1-PC0-Pad8)") (class "Default")
      (node (ref "U$1") (pin "8") (pinfunction "PC0_8") (pintype "bidirectional"))
    )
    (net (code "89") (name "unconnected-(U$1-PC1-Pad9)") (class "Default")
      (node (ref "U$1") (pin "9") (pinfunction "PC1_9") (pintype "bidirectional"))
    )
    (net (code "90") (name "unconnected-(U$1-PC2-Pad10)") (class "Default")
      (node (ref "U$1") (pin "10") (pinfunction "PC2_10") (pintype "bidirectional"))
    )
    (net (code "91") (name "unconnected-(U$1-PC3-Pad11)") (class "Default")
      (node (ref "U$1") (pin "11") (pinfunction "PC3_11") (pintype "bidirectional"))
    )
    (net (code "92") (name "unconnected-(U$1-PC4-Pad24)") (class "Default")
      (node (ref "U$1") (pin "24") (pinfunction "PC4_24") (pintype "bidirectional"))
    )
    (net (code "93") (name "unconnected-(U$1-PC5-Pad25)") (class "Default")
      (node (ref "U$1") (pin "25") (pinfunction "PC5_25") (pintype "bidirectional"))
    )
    (net (code "94") (name "unconnected-(U$1-PC6-Pad37)") (class "Default")
      (node (ref "U$1") (pin "37") (pinfunction "PC6_37") (pintype "bidirectional"))
    )
    (net (code "95") (name "unconnected-(U$1-PC7-Pad38)") (class "Default")
      (node (ref "U$1") (pin "38") (pinfunction "PC7_38") (pintype "bidirectional"))
    )
    (net (code "96") (name "unconnected-(U$1-PC8-Pad39)") (class "Default")
      (node (ref "U$1") (pin "39") (pinfunction "PC8_39") (pintype "bidirectional"))
    )
    (net (code "97") (name "unconnected-(U$1-PC9-Pad40)") (class "Default")
      (node (ref "U$1") (pin "40") (pinfunction "PC9_40") (pintype "bidirectional"))
    )
    (net (code "98") (name "unconnected-(U$1-PC10-Pad51)") (class "Default")
      (node (ref "U$1") (pin "51") (pinfunction "PC10_51") (pintype "bidirectional"))
    )
    (net (code "99") (name "unconnected-(U$1-PC11-Pad52)") (class "Default")
      (node (ref "U$1") (pin "52") (pinfunction "PC11_52") (pintype "bidirectional"))
    )
    (net (code "100") (name "unconnected-(U$1-PC12-Pad53)") (class "Default")
      (node (ref "U$1") (pin "53") (pinfunction "PC12_53") (pintype "bidirectional"))
    )
    (net (code "101") (name "unconnected-(U$1-PC13-Pad2)") (class "Default")
      (node (ref "U$1") (pin "2") (pinfunction "PC13_2") (pintype "bidirectional"))
    )
    (net (code "102") (name "unconnected-(U$1-PC14{slash}OSC32_IN-Pad3)") (class "Default")
      (node (ref "U$1") (pin "3") (pinfunction "PC14/OSC32_IN_3") (pintype "bidirectional"))
    )
    (net (code "103") (name "unconnected-(U$1-PC15{slash}OSC32_OUT-Pad4)") (class "Default")
      (node (ref "U$1") (pin "4") (pinfunction "PC15/OSC32_OUT_4") (pintype "bidirectional"))
    )
    (net (code "104") (name "unconnected-(U$1-PD2-Pad54)") (class "Default")
      (node (ref "U$1") (pin "54") (pinfunction "PD2_54") (pintype "bidirectional"))
    )
    (net (code "105") (name "unconnected-(U$1-VBAT-Pad1)") (class "Default")
      (node (ref "U$1") (pin "1") (pinfunction "VBAT_1") (pintype "bidirectional"))
    )
    (net (code "106") (name "unconnected-(U$1-VCAP1-Pad30)") (class "Default")
      (node (ref "U$1") (pin "30") (pinfunction "VCAP1_30") (pintype "bidirectional"))
    )
  )
)
